# M_D_ext_power_usb_centered.net
KiCad netlist of a schematic drawn in EAGLE
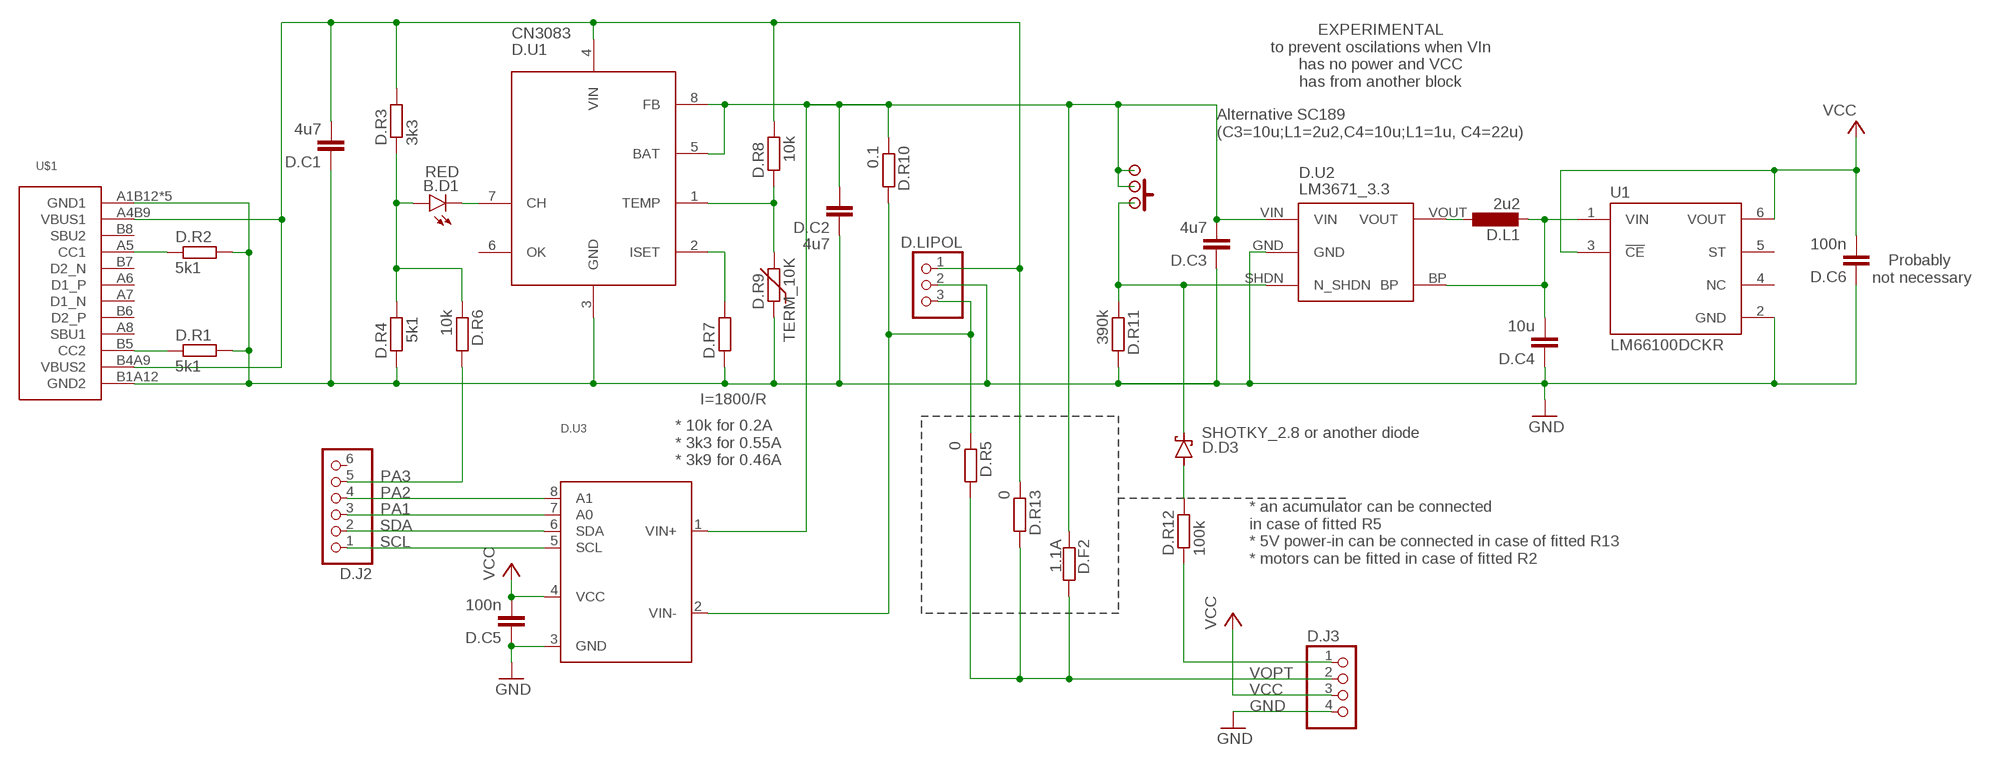
[diagram p0: schematic, sheet 1]

(export (version "E")
  (design (tool "Eeschema 10.0.6"))
  (components
    (comp (ref "B.D1")
      (value "RED")
      (footprint "eagle-import:CHIP-LED0603")
      (libsource (lib "eagle-import") (part "LEDCHIP-LED0603"))
    )
    (comp (ref "D.C1")
      (value "4u7")
      (footprint "eagle-import:C0603")
      (libsource (lib "eagle-import") (part "C-EUC0603"))
    )
    (comp (ref "D.C2")
      (value "4u7")
      (footprint "eagle-import:C0603")
      (libsource (lib "eagle-import") (part "C-EUC0603"))
    )
    (comp (ref "D.C3")
      (value "4u7")
      (footprint "eagle-import:C0603")
      (libsource (lib "eagle-import") (part "C-EUC0603"))
    )
    (comp (ref "D.C4")
      (value "10u")
      (footprint "eagle-import:C0603")
      (libsource (lib "eagle-import") (part "C-EUC0603"))
    )
    (comp (ref "D.C5")
      (value "100n")
      (footprint "eagle-import:C0603")
      (libsource (lib "eagle-import") (part "C-EUC0603"))
    )
    (comp (ref "D.C6")
      (value "100n")
      (footprint "eagle-import:C0603")
      (libsource (lib "eagle-import") (part "C-EUC0603"))
    )
    (comp (ref "D.D3")
      (value "SHOTKY_2.8 or another diode")
      (footprint "eagle-import:SHOTKY_2.8")
      (libsource (lib "eagle-import") (part "SHOTKY_2.8"))
    )
    (comp (ref "D.F2")
      (value "1.1A")
      (footprint "eagle-import:R0805")
      (libsource (lib "eagle-import") (part "R-EU_R0805"))
    )
    (comp (ref "D.J2")
      (value "PINHD-1X6")
      (footprint "eagle-import:1X06")
      (libsource (lib "eagle-import") (part "PINHD-1X6"))
    )
    (comp (ref "D.J3")
      (value "PINHD-1X4")
      (footprint "eagle-import:1X04")
      (libsource (lib "eagle-import") (part "PINHD-1X4"))
    )
    (comp (ref "D.L1")
      (value "2u2")
      (footprint "eagle-import:L3230M")
      (libsource (lib "eagle-import") (part "L-EUL3230M"))
    )
    (comp (ref "D.LIPOL")
      (value "PINHEAD-1X3-2")
      (footprint "eagle-import:1X-03-2")
      (libsource (lib "eagle-import") (part "PINHEAD-1X3-2"))
    )
    (comp (ref "D.ON/OFF/RESET")
      (value "SWITCH")
      (footprint "eagle-import:SWITCH")
      (libsource (lib "eagle-import") (part "SWITCH"))
    )
    (comp (ref "D.R1")
      (value "5k1")
      (footprint "eagle-import:R0603")
      (libsource (lib "eagle-import") (part "R-EU_R0603"))
    )
    (comp (ref "D.R2")
      (value "5k1")
      (footprint "eagle-import:R0603")
      (libsource (lib "eagle-import") (part "R-EU_R0603"))
    )
    (comp (ref "D.R3")
      (value "3k3")
      (footprint "eagle-import:R0603")
      (libsource (lib "eagle-import") (part "R-EU_R0603"))
    )
    (comp (ref "D.R4")
      (value "5k1")
      (footprint "eagle-import:R0603")
      (libsource (lib "eagle-import") (part "R-EU_R0603"))
    )
    (comp (ref "D.R5")
      (value "0")
      (footprint "eagle-import:R0603")
      (libsource (lib "eagle-import") (part "R-EU_R0603"))
    )
    (comp (ref "D.R6")
      (value "10k")
      (footprint "eagle-import:R0603")
      (libsource (lib "eagle-import") (part "R-EU_R0603"))
    )
    (comp (ref "D.R7")
      (value "I=1800/R")
      (footprint "eagle-import:R0603")
      (libsource (lib "eagle-import") (part "R-EU_R0603"))
    )
    (comp (ref "D.R8")
      (value "10k")
      (footprint "eagle-import:R0603")
      (libsource (lib "eagle-import") (part "R-EU_R0603"))
    )
    (comp (ref "D.R9")
      (value "TERM_10K")
      (footprint "eagle-import:THERM")
      (libsource (lib "eagle-import") (part "THERM"))
    )
    (comp (ref "D.R10")
      (value "0.1")
      (footprint "eagle-import:R0805")
      (libsource (lib "eagle-import") (part "R-EU_R0805"))
    )
    (comp (ref "D.R11")
      (value "390k")
      (footprint "eagle-import:R0603")
      (libsource (lib "eagle-import") (part "R-EU_R0603"))
    )
    (comp (ref "D.R12")
      (value "100k")
      (footprint "eagle-import:R0603")
      (libsource (lib "eagle-import") (part "R-EU_R0603"))
    )
    (comp (ref "D.R13")
      (value "0")
      (footprint "eagle-import:R0603")
      (libsource (lib "eagle-import") (part "R-EU_R0603"))
    )
    (comp (ref "D.U1")
      (value "CN3083")
      (footprint "eagle-import:SOP8")
      (libsource (lib "eagle-import") (part "CN3083"))
    )
    (comp (ref "D.U2")
      (value "LM3671_3.3")
      (footprint "eagle-import:SOT32-5")
      (libsource (lib "eagle-import") (part "STABILISER_APE8865"))
    )
    (comp (ref "D.U3")
      (value "INA219")
      (footprint "eagle-import:SOT23-8")
      (libsource (lib "eagle-import") (part "INA219"))
    )
    (comp (ref "U$1")
      (value "USB-C")
      (footprint "eagle-import:USB-C")
      (libsource (lib "eagle-import") (part "USB-C"))
    )
    (comp (ref "U1")
      (value "LM66100DCKR")
      (footprint "eagle-import:SOT65P210X110-6N")
      (fields (field (name "MF") "Texas Instruments"))
      (libsource (lib "eagle-import") (part "LM66100DCKR"))
    )
  )
  (nets
    (net (code "1") (name "/PA1") (class "Default")
      (node (ref "D.J2") (pin "3") (pinfunction "3_3") (pintype "passive"))
      (node (ref "D.U3") (pin "7") (pinfunction "A0_7") (pintype "bidirectional"))
    )
    (net (code "2") (name "/PA2") (class "Default")
      (node (ref "D.J2") (pin "4") (pinfunction "4_4") (pintype "passive"))
      (node (ref "D.U3") (pin "8") (pinfunction "A1_8") (pintype "bidirectional"))
    )
    (net (code "3") (name "/PA3") (class "Default")
      (node (ref "D.J2") (pin "5") (pinfunction "5_5") (pintype "passive"))
      (node (ref "D.R6") (pin "2") (pinfunction "2_2") (pintype "passive"))
    )
    (net (code "4") (name "/SCL") (class "Default")
      (node (ref "D.J2") (pin "1") (pinfunction "1_1") (pintype "passive"))
      (node (ref "D.U3") (pin "5") (pinfunction "SCL_5") (pintype "bidirectional"))
    )
    (net (code "5") (name "/SDA") (class "Default")
      (node (ref "D.J2") (pin "2") (pinfunction "2_2") (pintype "passive"))
      (node (ref "D.U3") (pin "6") (pinfunction "SDA_6") (pintype "bidirectional"))
    )
    (net (code "6") (name "/VOPT") (class "Default")
      (node (ref "D.F2") (pin "2") (pinfunction "2_2") (pintype "passive"))
      (node (ref "D.J3") (pin "2") (pinfunction "2_2") (pintype "passive"))
      (node (ref "D.R13") (pin "2") (pinfunction "2_2") (pintype "passive"))
      (node (ref "D.R5") (pin "2") (pinfunction "2_2") (pintype "passive"))
    )
    (net (code "7") (name "GND") (class "Default")
      (node (ref "D.C1") (pin "1") (pinfunction "1_1") (pintype "passive"))
      (node (ref "D.C2") (pin "1") (pinfunction "1_1") (pintype "passive"))
      (node (ref "D.C3") (pin "1") (pinfunction "1_1") (pintype "passive"))
      (node (ref "D.C4") (pin "1") (pinfunction "1_1") (pintype "passive"))
      (node (ref "D.C5") (pin "1") (pinfunction "1_1") (pintype "passive"))
      (node (ref "D.C6") (pin "1") (pinfunction "1_1") (pintype "passive"))
      (node (ref "D.J3") (pin "4") (pinfunction "4_4") (pintype "passive"))
      (node (ref "D.LIPOL") (pin "2") (pinfunction "2_2") (pintype "passive"))
      (node (ref "D.R1") (pin "2") (pinfunction "2_2") (pintype "passive"))
      (node (ref "D.R11") (pin "2") (pinfunction "2_2") (pintype "passive"))
      (node (ref "D.R2") (pin "2") (pinfunction "2_2") (pintype "passive"))
      (node (ref "D.R4") (pin "1") (pinfunction "1_1") (pintype "passive"))
      (node (ref "D.R7") (pin "1") (pinfunction "1_1") (pintype "passive"))
      (node (ref "D.R9") (pin "1") (pinfunction "1_1") (pintype "passive"))
      (node (ref "D.U1") (pin "3") (pinfunction "GND_3") (pintype "bidirectional"))
      (node (ref "D.U2") (pin "GND") (pinfunction "GND_GND") (pintype "bidirectional"))
      (node (ref "D.U3") (pin "3") (pinfunction "GND_3") (pintype "bidirectional"))
      (node (ref "U$1") (pin "A1B12") (pinfunction "GND1_A1B12") (pintype "bidirectional"))
      (node (ref "U$1") (pin "B1A12") (pinfunction "GND2_B1A12") (pintype "bidirectional"))
      (node (ref "U$1") (pin "SH1") (pinfunction "GND1_SH1") (pintype "bidirectional"))
      (node (ref "U$1") (pin "SH2") (pinfunction "GND1_SH2") (pintype "bidirectional"))
      (node (ref "U$1") (pin "SH3") (pinfunction "GND1_SH3") (pintype "bidirectional"))
      (node (ref "U$1") (pin "SH4") (pinfunction "GND1_SH4") (pintype "bidirectional"))
      (node (ref "U1") (pin "2") (pinfunction "GND_2") (pintype "power_in"))
    )
    (net (code "8") (name "Net-(B.D1-A)") (class "Default")
      (node (ref "B.D1") (pin "A1") (pinfunction "A_A1") (pintype "passive"))
      (node (ref "D.R3") (pin "1") (pinfunction "1_1") (pintype "passive"))
      (node (ref "D.R4") (pin "2") (pinfunction "2_2") (pintype "passive"))
      (node (ref "D.R6") (pin "1") (pinfunction "1_1") (pintype "passive"))
    )
    (net (code "9") (name "Net-(B.D1-C)") (class "Default")
      (node (ref "B.D1") (pin "C1") (pinfunction "C_C1") (pintype "passive"))
      (node (ref "D.U1") (pin "7") (pinfunction "CH_7") (pintype "bidirectional"))
    )
    (net (code "10") (name "Net-(D.D3-C)") (class "Default")
      (node (ref "D.D3") (pin "K") (pinfunction "C_K") (pintype "passive"))
      (node (ref "D.ON/OFF/RESET") (pin "P$1") (pinfunction "P$1_P$1") (pintype "bidirectional"))
      (node (ref "D.ON/OFF/RESET") (pin "P$5") (pinfunction "P$1_P$5") (pintype "bidirectional"))
      (node (ref "D.ON/OFF/RESET") (pin "P$7") (pinfunction "P$1_P$7") (pintype "bidirectional"))
      (node (ref "D.R11") (pin "1") (pinfunction "1_1") (pintype "passive"))
      (node (ref "D.U2") (pin "SHDN") (pinfunction "N_SHDN_SHDN") (pintype "bidirectional"))
    )
    (net (code "11") (name "Net-(D.D3-PadA)") (class "Default")
      (node (ref "D.D3") (pin "A") (pinfunction "A_A") (pintype "passive"))
      (node (ref "D.R12") (pin "2") (pinfunction "2_2") (pintype "passive"))
    )
    (net (code "12") (name "Net-(D.J3-Pad1)") (class "Default")
      (node (ref "D.J3") (pin "1") (pinfunction "1_1") (pintype "passive"))
      (node (ref "D.R12") (pin "1") (pinfunction "1_1") (pintype "passive"))
    )
    (net (code "13") (name "Net-(D.L1-Pad1)") (class "Default")
      (node (ref "D.L1") (pin "1") (pinfunction "1_1") (pintype "passive"))
      (node (ref "D.U2") (pin "VOUT") (pinfunction "VOUT_VOUT") (pintype "bidirectional"))
    )
    (net (code "14") (name "Net-(D.U1-BAT)") (class "Default")
      (node (ref "D.C2") (pin "2") (pinfunction "2_2") (pintype "passive"))
      (node (ref "D.C3") (pin "2") (pinfunction "2_2") (pintype "passive"))
      (node (ref "D.F2") (pin "1") (pinfunction "1_1") (pintype "passive"))
      (node (ref "D.ON/OFF/RESET") (pin "P$2") (pinfunction "P$2_P$2") (pintype "bidirectional"))
      (node (ref "D.ON/OFF/RESET") (pin "P$3") (pinfunction "P$3_P$3") (pintype "bidirectional"))
      (node (ref "D.ON/OFF/RESET") (pin "P$4") (pinfunction "P$3_P$4") (pintype "bidirectional"))
      (node (ref "D.ON/OFF/RESET") (pin "P$6") (pinfunction "P$3_P$6") (pintype "bidirectional"))
      (node (ref "D.R10") (pin "1") (pinfunction "1_1") (pintype "passive"))
      (node (ref "D.U1") (pin "5") (pinfunction "BAT_5") (pintype "bidirectional"))
      (node (ref "D.U1") (pin "8") (pinfunction "FB_8") (pintype "bidirectional"))
      (node (ref "D.U2") (pin "VIN") (pinfunction "VIN_VIN") (pintype "bidirectional"))
      (node (ref "D.U3") (pin "1") (pinfunction "VIN+_1") (pintype "bidirectional"))
    )
    (net (code "15") (name "Net-(D.U1-ISET)") (class "Default")
      (node (ref "D.R7") (pin "2") (pinfunction "2_2") (pintype "passive"))
      (node (ref "D.U1") (pin "2") (pinfunction "ISET_2") (pintype "bidirectional"))
    )
    (net (code "16") (name "Net-(D.U1-TEMP)") (class "Default")
      (node (ref "D.R8") (pin "1") (pinfunction "1_1") (pintype "passive"))
      (node (ref "D.R9") (pin "2") (pinfunction "2_2") (pintype "passive"))
      (node (ref "D.U1") (pin "1") (pinfunction "TEMP_1") (pintype "bidirectional"))
    )
    (net (code "17") (name "Net-(D.U1-VIN)") (class "Default")
      (node (ref "D.C1") (pin "2") (pinfunction "2_2") (pintype "passive"))
      (node (ref "D.LIPOL") (pin "1") (pinfunction "1_1") (pintype "passive"))
      (node (ref "D.R13") (pin "1") (pinfunction "1_1") (pintype "passive"))
      (node (ref "D.R3") (pin "2") (pinfunction "2_2") (pintype "passive"))
      (node (ref "D.R8") (pin "2") (pinfunction "2_2") (pintype "passive"))
      (node (ref "D.U1") (pin "4") (pinfunction "VIN_4") (pintype "bidirectional"))
      (node (ref "U$1") (pin "A4B9") (pinfunction "VBUS1_A4B9") (pintype "bidirectional"))
      (node (ref "U$1") (pin "B4A9") (pinfunction "VBUS2_B4A9") (pintype "bidirectional"))
    )
    (net (code "18") (name "Net-(D.U3-VIN-)") (class "Default")
      (node (ref "D.LIPOL") (pin "3") (pinfunction "3_3") (pintype "passive"))
      (node (ref "D.R10") (pin "2") (pinfunction "2_2") (pintype "passive"))
      (node (ref "D.R5") (pin "1") (pinfunction "1_1") (pintype "passive"))
      (node (ref "D.U3") (pin "2") (pinfunction "VIN-_2") (pintype "bidirectional"))
    )
    (net (code "19") (name "Net-(U$1-CC1)") (class "Default")
      (node (ref "D.R2") (pin "1") (pinfunction "1_1") (pintype "passive"))
      (node (ref "U$1") (pin "A5") (pinfunction "CC1_A5") (pintype "bidirectional"))
    )
    (net (code "20") (name "Net-(U$1-CC2)") (class "Default")
      (node (ref "D.R1") (pin "1") (pinfunction "1_1") (pintype "passive"))
      (node (ref "U$1") (pin "B5") (pinfunction "CC2_B5") (pintype "bidirectional"))
    )
    (net (code "21") (name "Net-(U1-VIN)") (class "Default")
      (node (ref "D.C4") (pin "2") (pinfunction "2_2") (pintype "passive"))
      (node (ref "D.L1") (pin "2") (pinfunction "2_2") (pintype "passive"))
      (node (ref "D.U2") (pin "BP") (pinfunction "BP_BP") (pintype "bidirectional"))
      (node (ref "U1") (pin "1") (pinfunction "VIN_1") (pintype "input"))
    )
    (net (code "22") (name "VCC") (class "Default")
      (node (ref "D.C5") (pin "2") (pinfunction "2_2") (pintype "passive"))
      (node (ref "D.C6") (pin "2") (pinfunction "2_2") (pintype "passive"))
      (node (ref "D.J3") (pin "3") (pinfunction "3_3") (pintype "passive"))
      (node (ref "D.U3") (pin "4") (pinfunction "VCC_4") (pintype "bidirectional"))
      (node (ref "U1") (pin "3") (pinfunction "~{CE}_3") (pintype "input"))
      (node (ref "U1") (pin "6") (pinfunction "VOUT_6") (pintype "output"))
    )
    (net (code "23") (name "unconnected-(D.J2-Pad6)") (class "Default")
      (node (ref "D.J2") (pin "6") (pinfunction "6_6") (pintype "passive"))
    )
    (net (code "24") (name "unconnected-(D.U1-OK-Pad6)") (class "Default")
      (node (ref "D.U1") (pin "6") (pinfunction "OK_6") (pintype "bidirectional"))
    )
    (net (code "25") (name "unconnected-(U$1-D1_N-PadA7)") (class "Default")
      (node (ref "U$1") (pin "A7") (pinfunction "D1_N_A7") (pintype "bidirectional"))
    )
    (net (code "26") (name "unconnected-(U$1-D1_P-PadA6)") (class "Default")
      (node (ref "U$1") (pin "A6") (pinfunction "D1_P_A6") (pintype "bidirectional"))
    )
    (net (code "27") (name "unconnected-(U$1-D2_N-PadB7)") (class "Default")
      (node (ref "U$1") (pin "B7") (pinfunction "D2_N_B7") (pintype "bidirectional"))
    )
    (net (code "28") (name "unconnected-(U$1-D2_P-PadB6)") (class "Default")
      (node (ref "U$1") (pin "B6") (pinfunction "D2_P_B6") (pintype "bidirectional"))
    )
    (net (code "29") (name "unconnected-(U$1-SBU1-PadA8)") (class "Default")
      (node (ref "U$1") (pin "A8") (pinfunction "SBU1_A8") (pintype "bidirectional"))
    )
    (net (code "30") (name "unconnected-(U$1-SBU2-PadB8)") (class "Default")
      (node (ref "U$1") (pin "B8") (pinfunction "SBU2_B8") (pintype "bidirectional"))
    )
    (net (code "31") (name "unconnected-(U1-NC-Pad4)") (class "Default")
      (node (ref "U1") (pin "4") (pinfunction "NC_4") (pintype "no_connect"))
    )
    (net (code "32") (name "unconnected-(U1-ST-Pad5)") (class "Default")
      (node (ref "U1") (pin "5") (pinfunction "ST_5") (pintype "output"))
    )
  )
)
